# D1_Breakout_-_LCD_SMD_Dupont.net
KiCad netlist of a schematic drawn in EAGLE
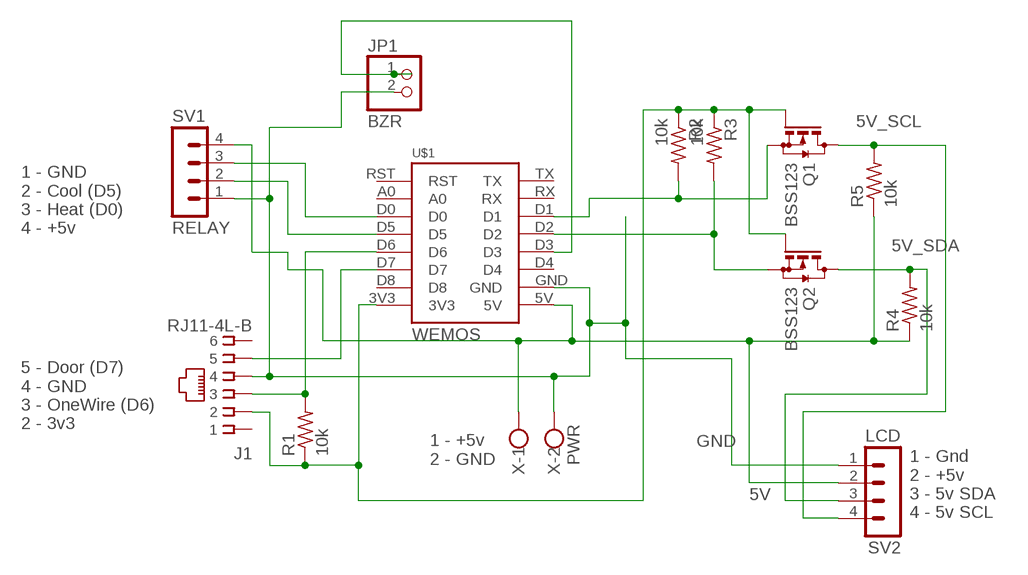
[diagram p0: schematic, sheet 1]

(export (version "E")
  (design (tool "Eeschema 10.0.6"))
  (components
    (comp (ref "J1")
      (value "RJ11-4L-B")
      (footprint "eagle-import:RJ11-NO_SHIELD")
      (fields (field (name "MF") "TYCO ELECTRONICS"))
      (libsource (lib "eagle-import") (part "RJ11-4L-B"))
    )
    (comp (ref "JP1")
      (value "BZR")
      (footprint "eagle-import:1X02")
      (libsource (lib "eagle-import") (part "PINHD-1X2"))
    )
    (comp (ref "Q1")
      (value "BSS123")
      (footprint "eagle-import:SOT23")
      (libsource (lib "eagle-import") (part "BSS123"))
    )
    (comp (ref "Q2")
      (value "BSS123")
      (footprint "eagle-import:SOT23")
      (libsource (lib "eagle-import") (part "BSS123"))
    )
    (comp (ref "R1")
      (value "10k")
      (footprint "eagle-import:R0805")
      (libsource (lib "eagle-import") (part "R-US_R0805"))
    )
    (comp (ref "R2")
      (value "10k")
      (footprint "eagle-import:R0805")
      (libsource (lib "eagle-import") (part "R-US_R0805"))
    )
    (comp (ref "R3")
      (value "10k")
      (footprint "eagle-import:R0805")
      (libsource (lib "eagle-import") (part "R-US_R0805"))
    )
    (comp (ref "R4")
      (value "10k")
      (footprint "eagle-import:R0805")
      (libsource (lib "eagle-import") (part "R-US_R0805"))
    )
    (comp (ref "R5")
      (value "10k")
      (footprint "eagle-import:R0805")
      (libsource (lib "eagle-import") (part "R-US_R0805"))
    )
    (comp (ref "SV1")
      (value "RELAY")
      (footprint "eagle-import:MA04-1")
      (libsource (lib "eagle-import") (part "MA04-1"))
    )
    (comp (ref "SV2")
      (value "LCD")
      (footprint "eagle-import:MA04-1")
      (libsource (lib "eagle-import") (part "MA04-1"))
    )
    (comp (ref "U$1")
      (value "WEMOS")
      (footprint "eagle-import:WEMOS")
      (libsource (lib "eagle-import") (part "WEMOS"))
    )
    (comp (ref "X")
      (value "PWR")
      (footprint "eagle-import:W237-102")
      (fields (field (name "MPN") "237-102"))
      (libsource (lib "eagle-import") (part "W237-102"))
    )
  )
  (nets
    (net (code "1") (name "/5V") (class "Default")
      (node (ref "R4") (pin "1") (pinfunction "1_1") (pintype "passive"))
      (node (ref "R5") (pin "1") (pinfunction "1_1") (pintype "passive"))
      (node (ref "SV1") (pin "4") (pinfunction "4_4") (pintype "passive"))
      (node (ref "SV2") (pin "2") (pinfunction "2_2") (pintype "passive"))
      (node (ref "U$1") (pin "5V") (pinfunction "5V_5V") (pintype "bidirectional"))
      (node (ref "X") (pin "1") (pinfunction "KL_1") (pintype "passive"))
    )
    (net (code "2") (name "/5V_SCL") (class "Default")
      (node (ref "Q1") (pin "3") (pinfunction "D_3") (pintype "passive"))
      (node (ref "R5") (pin "2") (pinfunction "2_2") (pintype "passive"))
      (node (ref "SV2") (pin "4") (pinfunction "4_4") (pintype "passive"))
    )
    (net (code "3") (name "/5V_SDA") (class "Default")
      (node (ref "Q2") (pin "3") (pinfunction "D_3") (pintype "passive"))
      (node (ref "R4") (pin "2") (pinfunction "2_2") (pintype "passive"))
      (node (ref "SV2") (pin "3") (pinfunction "3_3") (pintype "passive"))
    )
    (net (code "4") (name "/GND") (class "Default")
      (node (ref "J1") (pin "4") (pinfunction "4_4") (pintype "passive"))
      (node (ref "JP1") (pin "2") (pinfunction "2_2") (pintype "passive"))
      (node (ref "SV1") (pin "1") (pinfunction "1_1") (pintype "passive"))
      (node (ref "SV2") (pin "1") (pinfunction "1_1") (pintype "passive"))
      (node (ref "U$1") (pin "GND") (pinfunction "GND_GND") (pintype "bidirectional"))
      (node (ref "X") (pin "2") (pinfunction "KL_2") (pintype "passive"))
    )
    (net (code "5") (name "Net-(J1-Pad3)") (class "Default")
      (node (ref "J1") (pin "3") (pinfunction "3_3") (pintype "passive"))
      (node (ref "R1") (pin "2") (pinfunction "2_2") (pintype "passive"))
      (node (ref "U$1") (pin "D6") (pinfunction "D6_D6") (pintype "bidirectional"))
    )
    (net (code "6") (name "Net-(J1-Pad5)") (class "Default")
      (node (ref "J1") (pin "5") (pinfunction "5_5") (pintype "passive"))
      (node (ref "U$1") (pin "D7") (pinfunction "D7_D7") (pintype "bidirectional"))
    )
    (net (code "7") (name "Net-(JP1-Pad1)") (class "Default")
      (node (ref "JP1") (pin "1") (pinfunction "1_1") (pintype "passive"))
      (node (ref "U$1") (pin "D3") (pinfunction "D3_D3") (pintype "bidirectional"))
    )
    (net (code "8") (name "Net-(Q1-G)") (class "Default")
      (node (ref "J1") (pin "2") (pinfunction "2_2") (pintype "passive"))
      (node (ref "Q1") (pin "1") (pinfunction "G_1") (pintype "passive"))
      (node (ref "Q2") (pin "1") (pinfunction "G_1") (pintype "passive"))
      (node (ref "R1") (pin "1") (pinfunction "1_1") (pintype "passive"))
      (node (ref "R2") (pin "1") (pinfunction "1_1") (pintype "passive"))
      (node (ref "R3") (pin "1") (pinfunction "1_1") (pintype "passive"))
      (node (ref "U$1") (pin "3V3") (pinfunction "3V3_3V3") (pintype "bidirectional"))
    )
    (net (code "9") (name "Net-(Q1-S)") (class "Default")
      (node (ref "Q1") (pin "2") (pinfunction "S_2") (pintype "passive"))
      (node (ref "R2") (pin "2") (pinfunction "2_2") (pintype "passive"))
      (node (ref "U$1") (pin "D1") (pinfunction "D1_D1") (pintype "bidirectional"))
    )
    (net (code "10") (name "Net-(Q2-S)") (class "Default")
      (node (ref "Q2") (pin "2") (pinfunction "S_2") (pintype "passive"))
      (node (ref "R3") (pin "2") (pinfunction "2_2") (pintype "passive"))
      (node (ref "U$1") (pin "D2") (pinfunction "D2_D2") (pintype "bidirectional"))
    )
    (net (code "11") (name "Net-(SV1-Pad2)") (class "Default")
      (node (ref "SV1") (pin "2") (pinfunction "2_2") (pintype "passive"))
      (node (ref "U$1") (pin "D5") (pinfunction "D5_D5") (pintype "bidirectional"))
    )
    (net (code "12") (name "Net-(SV1-Pad3)") (class "Default")
      (node (ref "SV1") (pin "3") (pinfunction "3_3") (pintype "passive"))
      (node (ref "U$1") (pin "D0") (pinfunction "D0_D0") (pintype "bidirectional"))
    )
    (net (code "13") (name "unconnected-(J1-Pad1)") (class "Default")
      (node (ref "J1") (pin "1") (pinfunction "1_1") (pintype "passive"))
    )
    (net (code "14") (name "unconnected-(J1-Pad6)") (class "Default")
      (node (ref "J1") (pin "6") (pinfunction "6_6") (pintype "passive"))
    )
    (net (code "15") (name "unconnected-(U$1-PadA0)") (class "Default")
      (node (ref "U$1") (pin "A0") (pinfunction "A0_A0") (pintype "bidirectional"))
    )
    (net (code "16") (name "unconnected-(U$1-PadD4)") (class "Default")
      (node (ref "U$1") (pin "D4") (pinfunction "D4_D4") (pintype "bidirectional"))
    )
    (net (code "17") (name "unconnected-(U$1-PadD8)") (class "Default")
      (node (ref "U$1") (pin "D8") (pinfunction "D8_D8") (pintype "bidirectional"))
    )
    (net (code "18") (name "unconnected-(U$1-PadRST)") (class "Default")
      (node (ref "U$1") (pin "RST") (pinfunction "RST_RST") (pintype "bidirectional"))
    )
    (net (code "19") (name "unconnected-(U$1-PadRX)") (class "Default")
      (node (ref "U$1") (pin "RX") (pinfunction "RX_RX") (pintype "bidirectional"))
    )
    (net (code "20") (name "unconnected-(U$1-PadTX)") (class "Default")
      (node (ref "U$1") (pin "TX") (pinfunction "TX_TX") (pintype "bidirectional"))
    )
  )
)
